# Power.net
KiCad netlist of a schematic drawn in Altium Designer
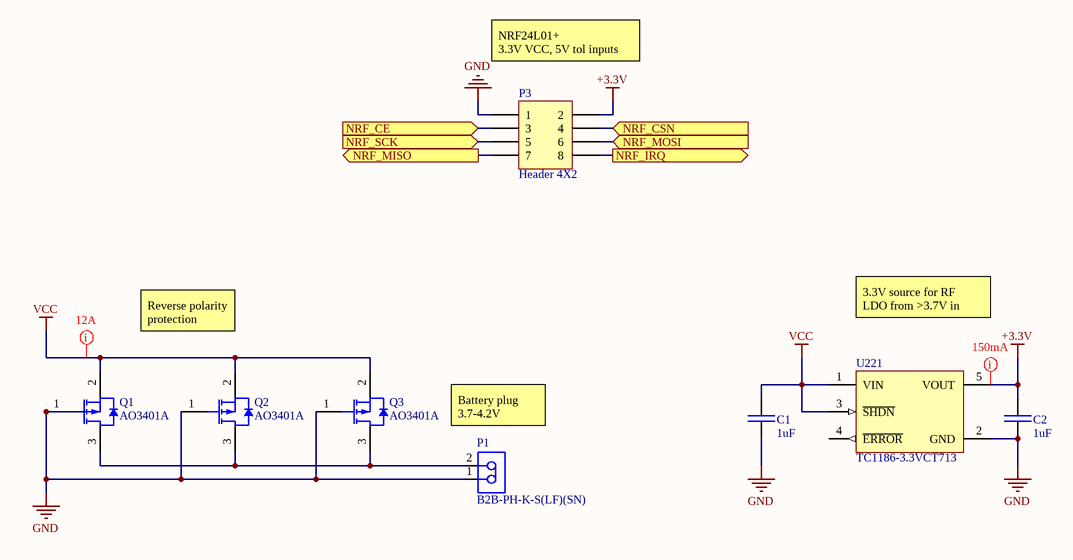
[diagram p0: Power.SchDoc]

(export (version "E")
  (design (tool "Eeschema 10.0.6"))
  (components
    (comp (ref "C1")
      (value "1uF")
      (footprint "CAPC2012X14M")
      (description "MULTILAYER CERAMIC CAPACITORS MLCC - SMD/SMT 1UF 50V 0805 ROHS")
      (fields (field (name "LCSC PART #") "C28323"))
      (libsource (lib "Schlib1") (part "CL21B105KBFNNNE_1"))
    )
    (comp (ref "C2")
      (value "1uF")
      (footprint "CAPC2012X14M")
      (description "MULTILAYER CERAMIC CAPACITORS MLCC - SMD/SMT 1UF 50V 0805 ROHS")
      (fields (field (name "LCSC PART #") "C28323"))
      (libsource (lib "Schlib1") (part "CL21B105KBFNNNE_1"))
    )
    (comp (ref "P1")
      (value "B2B-PH-K-S(LF)(SN)")
      (footprint "JST-B2B-PH-K-S_V")
      (fields (field (name "MANUFACTURER") "JST"))
      (libsource (lib "Altium Content Vault") (part "CN-2P-F-QF2"))
    )
    (comp (ref "P3")
      (value "Header 4X2")
      (footprint "HDR2X4")
      (description "Header, 4-Pin, Dual row")
      (fields (field (name "PUBLISHER") "Altium Limited"))
      (libsource (lib "Miscellaneous Connectors") (part "Header 4X2"))
    )
    (comp (ref "Q1")
      (value "AO3401A")
      (footprint "AO-SOT-23-3L_V")
      (description "P-Channel MOSFET, 30 V, 4 A, -55 to 150 degC, 3-Pin SOT-23-3L, RoHS, Tape and Reel")
      (fields (field (name "MANUFACTURER") "Alpha and Omega"))
      (libsource (lib "Altium Content Vault") (part "PEMOS-GSD-3"))
    )
    (comp (ref "Q2")
      (value "AO3401A")
      (footprint "AO-SOT-23-3L_V")
      (description "P-Channel MOSFET, 30 V, 4 A, -55 to 150 degC, 3-Pin SOT-23-3L, RoHS, Tape and Reel")
      (fields (field (name "MANUFACTURER") "Alpha and Omega"))
      (libsource (lib "Altium Content Vault") (part "PEMOS-GSD-3"))
    )
    (comp (ref "Q3")
      (value "AO3401A")
      (footprint "AO-SOT-23-3L_V")
      (description "P-Channel MOSFET, 30 V, 4 A, -55 to 150 degC, 3-Pin SOT-23-3L, RoHS, Tape and Reel")
      (fields (field (name "MANUFACTURER") "Alpha and Omega"))
      (libsource (lib "Altium Content Vault") (part "PEMOS-GSD-3"))
    )
    (comp (ref "U221")
      (value "TC1186-3.3VCT713")
      (footprint "SOT-23-CT5_L")
      (libsource (lib "Altium Content Vault") (part "PM-LINEREG-TC1054-IL5"))
    )
  )
  (nets
    (net (code "1") (name "+3.3V") (class "Default")
      (node (ref "C2") (pin "1") (pintype "passive"))
      (node (ref "P3") (pin "2") (pinfunction "2_2") (pintype "passive"))
      (node (ref "U221") (pin "5") (pinfunction "VOUT_5") (pintype "power_in"))
    )
    (net (code "2") (name "/NRF_CE") (class "Default")
      (node (ref "P3") (pin "3") (pinfunction "3_3") (pintype "passive"))
    )
    (net (code "3") (name "/NRF_CSN") (class "Default")
      (node (ref "P3") (pin "4") (pinfunction "4_4") (pintype "passive"))
    )
    (net (code "4") (name "/NRF_IRQ") (class "Default")
      (node (ref "P3") (pin "8") (pinfunction "8_8") (pintype "passive"))
    )
    (net (code "5") (name "/NRF_MISO") (class "Default")
      (node (ref "P3") (pin "7") (pinfunction "7_7") (pintype "passive"))
    )
    (net (code "6") (name "/NRF_MOSI") (class "Default")
      (node (ref "P3") (pin "6") (pinfunction "6_6") (pintype "passive"))
    )
    (net (code "7") (name "/NRF_SCK") (class "Default")
      (node (ref "P3") (pin "5") (pinfunction "5_5") (pintype "passive"))
    )
    (net (code "8") (name "GND") (class "Default")
      (node (ref "C1") (pin "2") (pintype "passive"))
      (node (ref "C2") (pin "2") (pintype "passive"))
      (node (ref "P1") (pin "1") (pinfunction "1_1") (pintype "passive"))
      (node (ref "P3") (pin "1") (pinfunction "1_1") (pintype "passive"))
      (node (ref "Q1") (pin "1") (pinfunction "GATE_1") (pintype "passive"))
      (node (ref "Q2") (pin "1") (pinfunction "GATE_1") (pintype "passive"))
      (node (ref "Q3") (pin "1") (pinfunction "GATE_1") (pintype "passive"))
      (node (ref "U221") (pin "2") (pinfunction "GND_2") (pintype "power_in"))
    )
    (net (code "9") (name "Net-(Q1-DRAIN)") (class "Default")
      (node (ref "P1") (pin "2") (pinfunction "2_2") (pintype "passive"))
      (node (ref "Q1") (pin "3") (pinfunction "DRAIN_3") (pintype "passive"))
      (node (ref "Q2") (pin "3") (pinfunction "DRAIN_3") (pintype "passive"))
      (node (ref "Q3") (pin "3") (pinfunction "DRAIN_3") (pintype "passive"))
    )
    (net (code "10") (name "VCC") (class "Default")
      (node (ref "C1") (pin "1") (pintype "passive"))
      (node (ref "Q1") (pin "2") (pinfunction "SOURCE_2") (pintype "passive"))
      (node (ref "Q2") (pin "2") (pinfunction "SOURCE_2") (pintype "passive"))
      (node (ref "Q3") (pin "2") (pinfunction "SOURCE_2") (pintype "passive"))
      (node (ref "U221") (pin "1") (pinfunction "VIN_1") (pintype "power_in"))
      (node (ref "U221") (pin "3") (pinfunction "~{SHDN}_3") (pintype "input"))
    )
    (net (code "11") (name "unconnected-(U221-~{ERROR}-Pad4)") (class "Default")
      (node (ref "U221") (pin "4") (pinfunction "~{ERROR}_4") (pintype "output"))
    )
  )
)
